# comicition.net
KiCad netlist of a schematic drawn in Altium Designer
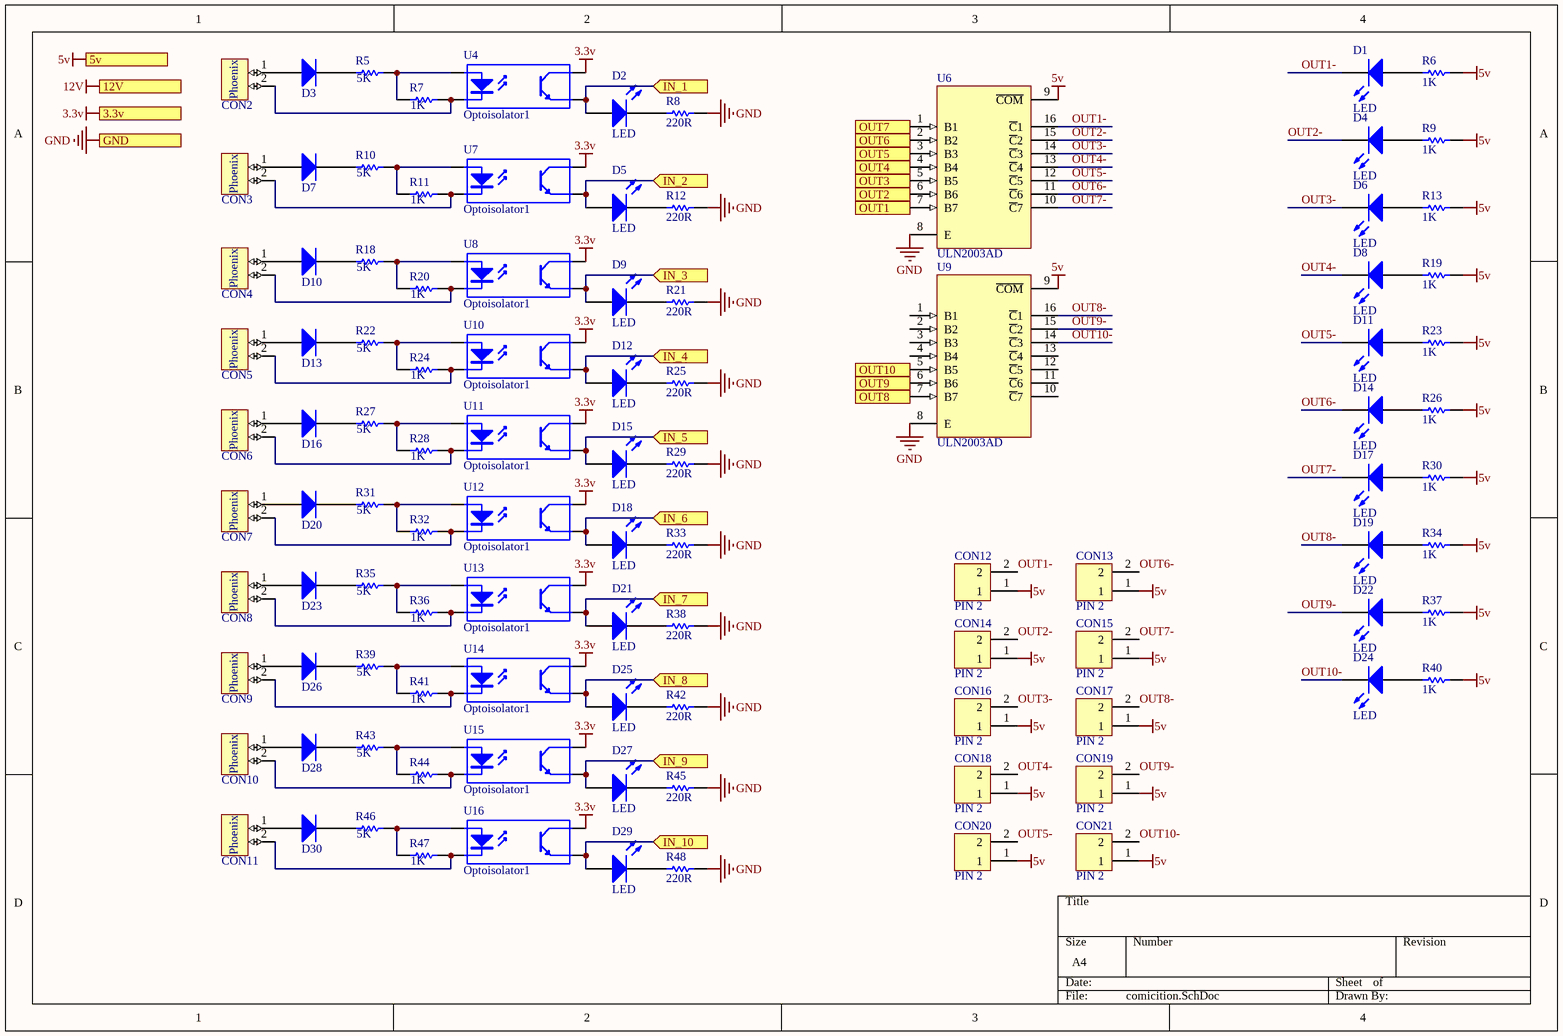
[diagram p0: comicition.SchDoc]

(export (version "E")
  (design (tool "Eeschema 10.0.6"))
  (components
    (comp (ref "CON2")
      (value "PHOENIX 2")
      (footprint "phonix 2")
      (libsource (lib "m_faryabi") (part "PHOENIX 2"))
    )
    (comp (ref "CON3")
      (value "PHOENIX 2")
      (footprint "phonix 2")
      (libsource (lib "m_faryabi") (part "PHOENIX 2"))
    )
    (comp (ref "CON4")
      (value "PHOENIX 2")
      (footprint "phonix 2")
      (libsource (lib "m_faryabi") (part "PHOENIX 2"))
    )
    (comp (ref "CON5")
      (value "PHOENIX 2")
      (footprint "phonix 2")
      (libsource (lib "m_faryabi") (part "PHOENIX 2"))
    )
    (comp (ref "CON6")
      (value "PHOENIX 2")
      (footprint "phonix 2")
      (libsource (lib "m_faryabi") (part "PHOENIX 2"))
    )
    (comp (ref "CON7")
      (value "PHOENIX 2")
      (footprint "phonix 2")
      (libsource (lib "m_faryabi") (part "PHOENIX 2"))
    )
    (comp (ref "CON8")
      (value "PHOENIX 2")
      (footprint "phonix 2")
      (libsource (lib "m_faryabi") (part "PHOENIX 2"))
    )
    (comp (ref "CON9")
      (value "PHOENIX 2")
      (footprint "phonix 2")
      (libsource (lib "m_faryabi") (part "PHOENIX 2"))
    )
    (comp (ref "CON10")
      (value "PHOENIX 2")
      (footprint "phonix 2")
      (libsource (lib "m_faryabi") (part "PHOENIX 2"))
    )
    (comp (ref "CON11")
      (value "PHOENIX 2")
      (footprint "phonix 2")
      (libsource (lib "m_faryabi") (part "PHOENIX 2"))
    )
    (comp (ref "CON12") (value "PIN 2") (footprint "PIN 2") (libsource (lib "m_faryabi") (part "PIN 2")))
    (comp (ref "CON13") (value "PIN 2") (footprint "PIN 2") (libsource (lib "m_faryabi") (part "PIN 2")))
    (comp (ref "CON14") (value "PIN 2") (footprint "PIN 2") (libsource (lib "m_faryabi") (part "PIN 2")))
    (comp (ref "CON15") (value "PIN 2") (footprint "PIN 2") (libsource (lib "m_faryabi") (part "PIN 2")))
    (comp (ref "CON16") (value "PIN 2") (footprint "PIN 2") (libsource (lib "m_faryabi") (part "PIN 2")))
    (comp (ref "CON17") (value "PIN 2") (footprint "PIN 2") (libsource (lib "m_faryabi") (part "PIN 2")))
    (comp (ref "CON18") (value "PIN 2") (footprint "PIN 2") (libsource (lib "m_faryabi") (part "PIN 2")))
    (comp (ref "CON19") (value "PIN 2") (footprint "PIN 2") (libsource (lib "m_faryabi") (part "PIN 2")))
    (comp (ref "CON20") (value "PIN 2") (footprint "PIN 2") (libsource (lib "m_faryabi") (part "PIN 2")))
    (comp (ref "CON21") (value "PIN 2") (footprint "PIN 2") (libsource (lib "m_faryabi") (part "PIN 2")))
    (comp (ref "D1") (value "LED") (footprint "led 5mm") (libsource (lib "m_faryabi") (part "LED")))
    (comp (ref "D2") (value "LED") (footprint "led 5mm") (libsource (lib "m_faryabi") (part "LED")))
    (comp (ref "D3")
      (value "1N4007")
      (footprint "RES 1206 (3216X08L)")
      (libsource (lib "m_faryabi") (part "1N4007"))
    )
    (comp (ref "D4") (value "LED") (footprint "led 5mm") (libsource (lib "m_faryabi") (part "LED")))
    (comp (ref "D5") (value "LED") (footprint "led 5mm") (libsource (lib "m_faryabi") (part "LED")))
    (comp (ref "D6") (value "LED") (footprint "led 5mm") (libsource (lib "m_faryabi") (part "LED")))
    (comp (ref "D7")
      (value "1N4007")
      (footprint "RES 1206 (3216X08L)")
      (libsource (lib "m_faryabi") (part "1N4007"))
    )
    (comp (ref "D8") (value "LED") (footprint "led 5mm") (libsource (lib "m_faryabi") (part "LED")))
    (comp (ref "D9") (value "LED") (footprint "led 5mm") (libsource (lib "m_faryabi") (part "LED")))
    (comp (ref "D10")
      (value "1N4007")
      (footprint "RES 1206 (3216X08L)")
      (libsource (lib "m_faryabi") (part "1N4007"))
    )
    (comp (ref "D11") (value "LED") (footprint "led 5mm") (libsource (lib "m_faryabi") (part "LED")))
    (comp (ref "D12") (value "LED") (footprint "led 5mm") (libsource (lib "m_faryabi") (part "LED")))
    (comp (ref "D13")
      (value "1N4007")
      (footprint "RES 1206 (3216X08L)")
      (libsource (lib "m_faryabi") (part "1N4007"))
    )
    (comp (ref "D14") (value "LED") (footprint "led 5mm") (libsource (lib "m_faryabi") (part "LED")))
    (comp (ref "D15") (value "LED") (footprint "led 5mm") (libsource (lib "m_faryabi") (part "LED")))
    (comp (ref "D16")
      (value "1N4007")
      (footprint "RES 1206 (3216X08L)")
      (libsource (lib "m_faryabi") (part "1N4007"))
    )
    (comp (ref "D17") (value "LED") (footprint "led 5mm") (libsource (lib "m_faryabi") (part "LED")))
    (comp (ref "D18") (value "LED") (footprint "led 5mm") (libsource (lib "m_faryabi") (part "LED")))
    (comp (ref "D19") (value "LED") (footprint "led 5mm") (libsource (lib "m_faryabi") (part "LED")))
    (comp (ref "D20")
      (value "1N4007")
      (footprint "RES 1206 (3216X08L)")
      (libsource (lib "m_faryabi") (part "1N4007"))
    )
    (comp (ref "D21") (value "LED") (footprint "led 5mm") (libsource (lib "m_faryabi") (part "LED")))
    (comp (ref "D22") (value "LED") (footprint "led 5mm") (libsource (lib "m_faryabi") (part "LED")))
    (comp (ref "D23")
      (value "1N4007")
      (footprint "RES 1206 (3216X08L)")
      (libsource (lib "m_faryabi") (part "1N4007"))
    )
    (comp (ref "D24") (value "LED") (footprint "led 5mm") (libsource (lib "m_faryabi") (part "LED")))
    (comp (ref "D25") (value "LED") (footprint "led 5mm") (libsource (lib "m_faryabi") (part "LED")))
    (comp (ref "D26")
      (value "1N4007")
      (footprint "RES 1206 (3216X08L)")
      (libsource (lib "m_faryabi") (part "1N4007"))
    )
    (comp (ref "D27") (value "LED") (footprint "led 5mm") (libsource (lib "m_faryabi") (part "LED")))
    (comp (ref "D28")
      (value "1N4007")
      (footprint "RES 1206 (3216X08L)")
      (libsource (lib "m_faryabi") (part "1N4007"))
    )
    (comp (ref "D29") (value "LED") (footprint "led 5mm") (libsource (lib "m_faryabi") (part "LED")))
    (comp (ref "D30")
      (value "1N4007")
      (footprint "RES 1206 (3216X08L)")
      (libsource (lib "m_faryabi") (part "1N4007"))
    )
    (comp (ref "R5")
      (value "5K")
      (footprint "RES 0805 (2012X06L)")
      (fields (field (name "Comment") "resistor"))
      (libsource (lib "m_faryabi") (part "resistor"))
    )
    (comp (ref "R6")
      (value "1K")
      (footprint "RES 0805 (2012X06L)")
      (fields (field (name "Comment") "resistor"))
      (libsource (lib "m_faryabi") (part "resistor"))
    )
    (comp (ref "R7")
      (value "1K")
      (footprint "RES 0805 (2012X06L)")
      (fields (field (name "Comment") "resistor"))
      (libsource (lib "m_faryabi") (part "resistor"))
    )
    (comp (ref "R8")
      (value "220R")
      (footprint "RES 0805 optional")
      (fields (field (name "Comment") "resistor"))
      (libsource (lib "m_faryabi") (part "resistor"))
    )
    (comp (ref "R9")
      (value "1K")
      (footprint "RES 0805 (2012X06L)")
      (fields (field (name "Comment") "resistor"))
      (libsource (lib "m_faryabi") (part "resistor"))
    )
    (comp (ref "R10")
      (value "5K")
      (footprint "RES 0805 (2012X06L)")
      (fields (field (name "Comment") "resistor"))
      (libsource (lib "m_faryabi") (part "resistor"))
    )
    (comp (ref "R11")
      (value "1K")
      (footprint "RES 0805 (2012X06L)")
      (fields (field (name "Comment") "resistor"))
      (libsource (lib "m_faryabi") (part "resistor"))
    )
    (comp (ref "R12")
      (value "220R")
      (footprint "RES 0805 optional")
      (fields (field (name "Comment") "resistor"))
      (libsource (lib "m_faryabi") (part "resistor"))
    )
    (comp (ref "R13")
      (value "1K")
      (footprint "RES 0805 (2012X06L)")
      (fields (field (name "Comment") "resistor"))
      (libsource (lib "m_faryabi") (part "resistor"))
    )
    (comp (ref "R18")
      (value "5K")
      (footprint "RES 0805 (2012X06L)")
      (fields (field (name "Comment") "resistor"))
      (libsource (lib "m_faryabi") (part "resistor"))
    )
    (comp (ref "R19")
      (value "1K")
      (footprint "RES 0805 (2012X06L)")
      (fields (field (name "Comment") "resistor"))
      (libsource (lib "m_faryabi") (part "resistor"))
    )
    (comp (ref "R20")
      (value "1K")
      (footprint "RES 0805 (2012X06L)")
      (fields (field (name "Comment") "resistor"))
      (libsource (lib "m_faryabi") (part "resistor"))
    )
    (comp (ref "R21")
      (value "220R")
      (footprint "RES 0805 optional")
      (fields (field (name "Comment") "resistor"))
      (libsource (lib "m_faryabi") (part "resistor"))
    )
    (comp (ref "R22")
      (value "5K")
      (footprint "RES 0805 (2012X06L)")
      (fields (field (name "Comment") "resistor"))
      (libsource (lib "m_faryabi") (part "resistor"))
    )
    (comp (ref "R23")
      (value "1K")
      (footprint "RES 0805 (2012X06L)")
      (fields (field (name "Comment") "resistor"))
      (libsource (lib "m_faryabi") (part "resistor"))
    )
    (comp (ref "R24")
      (value "1K")
      (footprint "RES 0805 (2012X06L)")
      (fields (field (name "Comment") "resistor"))
      (libsource (lib "m_faryabi") (part "resistor"))
    )
    (comp (ref "R25")
      (value "220R")
      (footprint "RES 0805 optional")
      (fields (field (name "Comment") "resistor"))
      (libsource (lib "m_faryabi") (part "resistor"))
    )
    (comp (ref "R26")
      (value "1K")
      (footprint "RES 0805 (2012X06L)")
      (fields (field (name "Comment") "resistor"))
      (libsource (lib "m_faryabi") (part "resistor"))
    )
    (comp (ref "R27")
      (value "5K")
      (footprint "RES 0805 (2012X06L)")
      (fields (field (name "Comment") "resistor"))
      (libsource (lib "m_faryabi") (part "resistor"))
    )
    (comp (ref "R28")
      (value "1K")
      (footprint "RES 0805 (2012X06L)")
      (fields (field (name "Comment") "resistor"))
      (libsource (lib "m_faryabi") (part "resistor"))
    )
    (comp (ref "R29")
      (value "220R")
      (footprint "RES 0805 optional")
      (fields (field (name "Comment") "resistor"))
      (libsource (lib "m_faryabi") (part "resistor"))
    )
    (comp (ref "R30")
      (value "1K")
      (footprint "RES 0805 (2012X06L)")
      (fields (field (name "Comment") "resistor"))
      (libsource (lib "m_faryabi") (part "resistor"))
    )
    (comp (ref "R31")
      (value "5K")
      (footprint "RES 0805 (2012X06L)")
      (fields (field (name "Comment") "resistor"))
      (libsource (lib "m_faryabi") (part "resistor"))
    )
    (comp (ref "R32")
      (value "1K")
      (footprint "RES 0805 (2012X06L)")
      (fields (field (name "Comment") "resistor"))
      (libsource (lib "m_faryabi") (part "resistor"))
    )
    (comp (ref "R33")
      (value "220R")
      (footprint "RES 0805 optional")
      (fields (field (name "Comment") "resistor"))
      (libsource (lib "m_faryabi") (part "resistor"))
    )
    (comp (ref "R34")
      (value "1K")
      (footprint "RES 0805 (2012X06L)")
      (fields (field (name "Comment") "resistor"))
      (libsource (lib "m_faryabi") (part "resistor"))
    )
    (comp (ref "R35")
      (value "5K")
      (footprint "RES 0805 (2012X06L)")
      (fields (field (name "Comment") "resistor"))
      (libsource (lib "m_faryabi") (part "resistor"))
    )
    (comp (ref "R36")
      (value "1K")
      (footprint "RES 0805 (2012X06L)")
      (fields (field (name "Comment") "resistor"))
      (libsource (lib "m_faryabi") (part "resistor"))
    )
    (comp (ref "R37")
      (value "1K")
      (footprint "RES 0805 (2012X06L)")
      (fields (field (name "Comment") "resistor"))
      (libsource (lib "m_faryabi") (part "resistor"))
    )
    (comp (ref "R38")
      (value "220R")
      (footprint "RES 0805 optional")
      (fields (field (name "Comment") "resistor"))
      (libsource (lib "m_faryabi") (part "resistor"))
    )
    (comp (ref "R39")
      (value "5K")
      (footprint "RES 0805 (2012X06L)")
      (fields (field (name "Comment") "resistor"))
      (libsource (lib "m_faryabi") (part "resistor"))
    )
    (comp (ref "R40")
      (value "1K")
      (footprint "RES 0805 (2012X06L)")
      (fields (field (name "Comment") "resistor"))
      (libsource (lib "m_faryabi") (part "resistor"))
    )
    (comp (ref "R41")
      (value "1K")
      (footprint "RES 0805 (2012X06L)")
      (fields (field (name "Comment") "resistor"))
      (libsource (lib "m_faryabi") (part "resistor"))
    )
    (comp (ref "R42")
      (value "220R")
      (footprint "RES 0805 optional")
      (fields (field (name "Comment") "resistor"))
      (libsource (lib "m_faryabi") (part "resistor"))
    )
    (comp (ref "R43")
      (value "5K")
      (footprint "RES 0805 (2012X06L)")
      (fields (field (name "Comment") "resistor"))
      (libsource (lib "m_faryabi") (part "resistor"))
    )
    (comp (ref "R44")
      (value "1K")
      (footprint "RES 0805 (2012X06L)")
      (fields (field (name "Comment") "resistor"))
      (libsource (lib "m_faryabi") (part "resistor"))
    )
    (comp (ref "R45")
      (value "220R")
      (footprint "RES 0805 optional")
      (fields (field (name "Comment") "resistor"))
      (libsource (lib "m_faryabi") (part "resistor"))
    )
    (comp (ref "R46")
      (value "5K")
      (footprint "RES 0805 (2012X06L)")
      (fields (field (name "Comment") "resistor"))
      (libsource (lib "m_faryabi") (part "resistor"))
    )
    (comp (ref "R47")
      (value "1K")
      (footprint "RES 0805 (2012X06L)")
      (fields (field (name "Comment") "resistor"))
      (libsource (lib "m_faryabi") (part "resistor"))
    )
    (comp (ref "R48")
      (value "220R")
      (footprint "RES 0805 optional")
      (fields (field (name "Comment") "resistor"))
      (libsource (lib "m_faryabi") (part "resistor"))
    )
    (comp (ref "U4")
      (value "Optoisolator1")
      (footprint "DIP-4")
      (description "4-Pin Phototransistor Optocoupler")
      (fields (field (name "PUBLISHER") "Altium Limited"))
      (libsource (lib "Miscellaneous Devices") (part "Optoisolator1"))
    )
    (comp (ref "U6")
      (value "ULN2003AD")
      (footprint "D016_N")
      (description "Darlington Transistor Array")
      (fields (field (name "PUBLISHER") "Altium Limited"))
      (libsource (lib "TI Interface Darlington Driver") (part "ULN2003AD"))
    )
    (comp (ref "U7")
      (value "Optoisolator1")
      (footprint "DIP-4")
      (description "4-Pin Phototransistor Optocoupler")
      (fields (field (name "PUBLISHER") "Altium Limited"))
      (libsource (lib "Miscellaneous Devices") (part "Optoisolator1"))
    )
    (comp (ref "U8")
      (value "Optoisolator1")
      (footprint "DIP-4")
      (description "4-Pin Phototransistor Optocoupler")
      (fields (field (name "PUBLISHER") "Altium Limited"))
      (libsource (lib "Miscellaneous Devices") (part "Optoisolator1"))
    )
    (comp (ref "U9")
      (value "ULN2003AD")
      (footprint "D016_N")
      (description "Darlington Transistor Array")
      (fields (field (name "PUBLISHER") "Altium Limited"))
      (libsource (lib "TI Interface Darlington Driver") (part "ULN2003AD"))
    )
    (comp (ref "U10")
      (value "Optoisolator1")
      (footprint "DIP-4")
      (description "4-Pin Phototransistor Optocoupler")
      (fields (field (name "PUBLISHER") "Altium Limited"))
      (libsource (lib "Miscellaneous Devices") (part "Optoisolator1"))
    )
    (comp (ref "U11")
      (value "Optoisolator1")
      (footprint "DIP-4")
      (description "4-Pin Phototransistor Optocoupler")
      (fields (field (name "PUBLISHER") "Altium Limited"))
      (libsource (lib "Miscellaneous Devices") (part "Optoisolator1"))
    )
    (comp (ref "U12")
      (value "Optoisolator1")
      (footprint "DIP-4")
      (description "4-Pin Phototransistor Optocoupler")
      (fields (field (name "PUBLISHER") "Altium Limited"))
      (libsource (lib "Miscellaneous Devices") (part "Optoisolator1"))
    )
    (comp (ref "U13")
      (value "Optoisolator1")
      (footprint "DIP-4")
      (description "4-Pin Phototransistor Optocoupler")
      (fields (field (name "PUBLISHER") "Altium Limited"))
      (libsource (lib "Miscellaneous Devices") (part "Optoisolator1"))
    )
    (comp (ref "U14")
      (value "Optoisolator1")
      (footprint "DIP-4")
      (description "4-Pin Phototransistor Optocoupler")
      (fields (field (name "PUBLISHER") "Altium Limited"))
      (libsource (lib "Miscellaneous Devices") (part "Optoisolator1"))
    )
    (comp (ref "U15")
      (value "Optoisolator1")
      (footprint "DIP-4")
      (description "4-Pin Phototransistor Optocoupler")
      (fields (field (name "PUBLISHER") "Altium Limited"))
      (libsource (lib "Miscellaneous Devices") (part "Optoisolator1"))
    )
    (comp (ref "U16")
      (value "Optoisolator1")
      (footprint "DIP-4")
      (description "4-Pin Phototransistor Optocoupler")
      (fields (field (name "PUBLISHER") "Altium Limited"))
      (libsource (lib "Miscellaneous Devices") (part "Optoisolator1"))
    )
  )
  (nets
    (net (code "1") (name "/IN_1") (class "Default")
      (node (ref "D2") (pin "1") (pinfunction "A_1") (pintype "passive"))
      (node (ref "U4") (pin "3") (pinfunction "E_3") (pintype "passive"))
    )
    (net (code "2") (name "/IN_2") (class "Default")
      (node (ref "D5") (pin "1") (pinfunction "A_1") (pintype "passive"))
      (node (ref "U7") (pin "3") (pinfunction "E_3") (pintype "passive"))
    )
    (net (code "3") (name "/IN_3") (class "Default")
      (node (ref "D9") (pin "1") (pinfunction "A_1") (pintype "passive"))
      (node (ref "U8") (pin "3") (pinfunction "E_3") (pintype "passive"))
    )
    (net (code "4") (name "/IN_4") (class "Default")
      (node (ref "D12") (pin "1") (pinfunction "A_1") (pintype "passive"))
      (node (ref "U10") (pin "3") (pinfunction "E_3") (pintype "passive"))
    )
    (net (code "5") (name "/IN_5") (class "Default")
      (node (ref "D15") (pin "1") (pinfunction "A_1") (pintype "passive"))
      (node (ref "U11") (pin "3") (pinfunction "E_3") (pintype "passive"))
    )
    (net (code "6") (name "/IN_6") (class "Default")
      (node (ref "D18") (pin "1") (pinfunction "A_1") (pintype "passive"))
      (node (ref "U12") (pin "3") (pinfunction "E_3") (pintype "passive"))
    )
    (net (code "7") (name "/IN_7") (class "Default")
      (node (ref "D21") (pin "1") (pinfunction "A_1") (pintype "passive"))
      (node (ref "U13") (pin "3") (pinfunction "E_3") (pintype "passive"))
    )
    (net (code "8") (name "/IN_8") (class "Default")
      (node (ref "D25") (pin "1") (pinfunction "A_1") (pintype "passive"))
      (node (ref "U14") (pin "3") (pinfunction "E_3") (pintype "passive"))
    )
    (net (code "9") (name "/IN_9") (class "Default")
      (node (ref "D27") (pin "1") (pinfunction "A_1") (pintype "passive"))
      (node (ref "U15") (pin "3") (pinfunction "E_3") (pintype "passive"))
    )
    (net (code "10") (name "/IN_10") (class "Default")
      (node (ref "D29") (pin "1") (pinfunction "A_1") (pintype "passive"))
      (node (ref "U16") (pin "3") (pinfunction "E_3") (pintype "passive"))
    )
    (net (code "11") (name "/OUT1") (class "Default")
      (node (ref "U6") (pin "7") (pinfunction "B7_7") (pintype "input"))
    )
    (net (code "12") (name "/OUT1-") (class "Default")
      (node (ref "CON12") (pin "2") (pinfunction "2_2") (pintype "passive"))
      (node (ref "D1") (pin "2") (pinfunction "K_2") (pintype "passive"))
      (node (ref "U6") (pin "16") (pinfunction "~{C}1_16") (pintype "open_collector"))
    )
    (net (code "13") (name "/OUT2") (class "Default")
      (node (ref "U6") (pin "6") (pinfunction "B6_6") (pintype "input"))
    )
    (net (code "14") (name "/OUT2-") (class "Default")
      (node (ref "CON14") (pin "2") (pinfunction "2_2") (pintype "passive"))
      (node (ref "D4") (pin "2") (pinfunction "K_2") (pintype "passive"))
      (node (ref "U6") (pin "15") (pinfunction "~{C}2_15") (pintype "open_collector"))
    )
    (net (code "15") (name "/OUT3") (class "Default")
      (node (ref "U6") (pin "5") (pinfunction "B5_5") (pintype "input"))
    )
    (net (code "16") (name "/OUT3-") (class "Default")
      (node (ref "CON16") (pin "2") (pinfunction "2_2") (pintype "passive"))
      (node (ref "D6") (pin "2") (pinfunction "K_2") (pintype "passive"))
      (node (ref "U6") (pin "14") (pinfunction "~{C}3_14") (pintype "open_collector"))
    )
    (net (code "17") (name "/OUT4") (class "Default")
      (node (ref "U6") (pin "4") (pinfunction "B4_4") (pintype "input"))
    )
    (net (code "18") (name "/OUT4-") (class "Default")
      (node (ref "CON18") (pin "2") (pinfunction "2_2") (pintype "passive"))
      (node (ref "D8") (pin "2") (pinfunction "K_2") (pintype "passive"))
      (node (ref "U6") (pin "13") (pinfunction "~{C}4_13") (pintype "open_collector"))
    )
    (net (code "19") (name "/OUT5") (class "Default")
      (node (ref "U6") (pin "3") (pinfunction "B3_3") (pintype "input"))
    )
    (net (code "20") (name "/OUT5-") (class "Default")
      (node (ref "CON20") (pin "2") (pinfunction "2_2") (pintype "passive"))
      (node (ref "D11") (pin "2") (pinfunction "K_2") (pintype "passive"))
      (node (ref "U6") (pin "12") (pinfunction "~{C}5_12") (pintype "open_collector"))
    )
    (net (code "21") (name "/OUT6") (class "Default")
      (node (ref "U6") (pin "2") (pinfunction "B2_2") (pintype "input"))
    )
    (net (code "22") (name "/OUT6-") (class "Default")
      (node (ref "CON13") (pin "2") (pinfunction "2_2") (pintype "passive"))
      (node (ref "D14") (pin "2") (pinfunction "K_2") (pintype "passive"))
      (node (ref "U6") (pin "11") (pinfunction "~{C}6_11") (pintype "open_collector"))
    )
    (net (code "23") (name "/OUT7") (class "Default")
      (node (ref "U6") (pin "1") (pinfunction "B1_1") (pintype "input"))
    )
    (net (code "24") (name "/OUT7-") (class "Default")
      (node (ref "CON15") (pin "2") (pinfunction "2_2") (pintype "passive"))
      (node (ref "D17") (pin "2") (pinfunction "K_2") (pintype "passive"))
      (node (ref "U6") (pin "10") (pinfunction "~{C}7_10") (pintype "open_collector"))
    )
    (net (code "25") (name "/OUT8") (class "Default")
      (node (ref "U9") (pin "7") (pinfunction "B7_7") (pintype "input"))
    )
    (net (code "26") (name "/OUT8-") (class "Default")
      (node (ref "CON17") (pin "2") (pinfunction "2_2") (pintype "passive"))
      (node (ref "D19") (pin "2") (pinfunction "K_2") (pintype "passive"))
      (node (ref "U9") (pin "16") (pinfunction "~{C}1_16") (pintype "open_collector"))
    )
    (net (code "27") (name "/OUT9") (class "Default")
      (node (ref "U9") (pin "6") (pinfunction "B6_6") (pintype "input"))
    )
    (net (code "28") (name "/OUT9-") (class "Default")
      (node (ref "CON19") (pin "2") (pinfunction "2_2") (pintype "passive"))
      (node (ref "D22") (pin "2") (pinfunction "K_2") (pintype "passive"))
      (node (ref "U9") (pin "15") (pinfunction "~{C}2_15") (pintype "open_collector"))
    )
    (net (code "29") (name "/OUT10") (class "Default")
      (node (ref "U9") (pin "5") (pinfunction "B5_5") (pintype "input"))
    )
    (net (code "30") (name "/OUT10-") (class "Default")
      (node (ref "CON21") (pin "2") (pinfunction "2_2") (pintype "passive"))
      (node (ref "D24") (pin "2") (pinfunction "K_2") (pintype "passive"))
      (node (ref "U9") (pin "14") (pinfunction "~{C}3_14") (pintype "open_collector"))
    )
    (net (code "31") (name "3.3v") (class "Default")
      (node (ref "U10") (pin "4") (pinfunction "C_4") (pintype "passive"))
      (node (ref "U11") (pin "4") (pinfunction "C_4") (pintype "passive"))
      (node (ref "U12") (pin "4") (pinfunction "C_4") (pintype "passive"))
      (node (ref "U13") (pin "4") (pinfunction "C_4") (pintype "passive"))
      (node (ref "U14") (pin "4") (pinfunction "C_4") (pintype "passive"))
      (node (ref "U15") (pin "4") (pinfunction "C_4") (pintype "passive"))
      (node (ref "U16") (pin "4") (pinfunction "C_4") (pintype "passive"))
      (node (ref "U4") (pin "4") (pinfunction "C_4") (pintype "passive"))
      (node (ref "U7") (pin "4") (pinfunction "C_4") (pintype "passive"))
      (node (ref "U8") (pin "4") (pinfunction "C_4") (pintype "passive"))
    )
    (net (code "32") (name "5v") (class "Default")
      (node (ref "CON12") (pin "1") (pinfunction "1_1") (pintype "passive"))
      (node (ref "CON13") (pin "1") (pinfunction "1_1") (pintype "passive"))
      (node (ref "CON14") (pin "1") (pinfunction "1_1") (pintype "passive"))
      (node (ref "CON15") (pin "1") (pinfunction "1_1") (pintype "passive"))
      (node (ref "CON16") (pin "1") (pinfunction "1_1") (pintype "passive"))
      (node (ref "CON17") (pin "1") (pinfunction "1_1") (pintype "passive"))
      (node (ref "CON18") (pin "1") (pinfunction "1_1") (pintype "passive"))
      (node (ref "CON19") (pin "1") (pinfunction "1_1") (pintype "passive"))
      (node (ref "CON20") (pin "1") (pinfunction "1_1") (pintype "passive"))
      (node (ref "CON21") (pin "1") (pinfunction "1_1") (pintype "passive"))
      (node (ref "R13") (pin "2") (pinfunction "2_2") (pintype "passive"))
      (node (ref "R19") (pin "2") (pinfunction "2_2") (pintype "passive"))
      (node (ref "R23") (pin "2") (pinfunction "2_2") (pintype "passive"))
      (node (ref "R26") (pin "2") (pinfunction "2_2") (pintype "passive"))
      (node (ref "R30") (pin "2") (pinfunction "2_2") (pintype "passive"))
      (node (ref "R34") (pin "2") (pinfunction "2_2") (pintype "passive"))
      (node (ref "R37") (pin "2") (pinfunction "2_2") (pintype "passive"))
      (node (ref "R40") (pin "2") (pinfunction "2_2") (pintype "passive"))
      (node (ref "R6") (pin "2") (pinfunction "2_2") (pintype "passive"))
      (node (ref "R9") (pin "2") (pinfunction "2_2") (pintype "passive"))
      (node (ref "U6") (pin "9") (pinfunction "~{COM}_9") (pintype "passive"))
      (node (ref "U9") (pin "9") (pinfunction "~{COM}_9") (pintype "passive"))
    )
    (net (code "34") (name "GND") (class "Default")
      (node (ref "R12") (pin "1") (pinfunction "1_1") (pintype "passive"))
      (node (ref "R21") (pin "1") (pinfunction "1_1") (pintype "passive"))
      (node (ref "R25") (pin "1") (pinfunction "1_1") (pintype "passive"))
      (node (ref "R29") (pin "1") (pinfunction "1_1") (pintype "passive"))
      (node (ref "R33") (pin "1") (pinfunction "1_1") (pintype "passive"))
      (node (ref "R38") (pin "1") (pinfunction "1_1") (pintype "passive"))
      (node (ref "R42") (pin "1") (pinfunction "1_1") (pintype "passive"))
      (node (ref "R45") (pin "1") (pinfunction "1_1") (pintype "passive"))
      (node (ref "R48") (pin "1") (pinfunction "1_1") (pintype "passive"))
      (node (ref "R8") (pin "1") (pinfunction "1_1") (pintype "passive"))
      (node (ref "U6") (pin "8") (pinfunction "E_8") (pintype "power_in"))
      (node (ref "U9") (pin "8") (pinfunction "E_8") (pintype "power_in"))
    )
    (net (code "35") (name "Net-(D1-A)") (class "Default")
      (node (ref "D1") (pin "1") (pinfunction "A_1") (pintype "passive"))
      (node (ref "R6") (pin "1") (pinfunction "1_1") (pintype "passive"))
    )
    (net (code "36") (name "Net-(D2-K)") (class "Default")
      (node (ref "D2") (pin "2") (pinfunction "K_2") (pintype "passive"))
      (node (ref "R8") (pin "2") (pinfunction "2_2") (pintype "passive"))
    )
    (net (code "37") (name "Net-(D3-A)") (class "Default")
      (node (ref "CON2") (pin "1") (pinfunction "1_1") (pintype "bidirectional"))
      (node (ref "D3") (pin "1") (pinfunction "A_1") (pintype "passive"))
    )
    (net (code "38") (name "Net-(D3-K)") (class "Default")
      (node (ref "D3") (pin "2") (pinfunction "K_2") (pintype "passive"))
      (node (ref "R5") (pin "1") (pinfunction "1_1") (pintype "passive"))
    )
    (net (code "39") (name "Net-(D4-A)") (class "Default")
      (node (ref "D4") (pin "1") (pinfunction "A_1") (pintype "passive"))
      (node (ref "R9") (pin "1") (pinfunction "1_1") (pintype "passive"))
    )
    (net (code "40") (name "Net-(D5-K)") (class "Default")
      (node (ref "D5") (pin "2") (pinfunction "K_2") (pintype "passive"))
      (node (ref "R12") (pin "2") (pinfunction "2_2") (pintype "passive"))
    )
    (net (code "41") (name "Net-(D6-A)") (class "Default")
      (node (ref "D6") (pin "1") (pinfunction "A_1") (pintype "passive"))
      (node (ref "R13") (pin "1") (pinfunction "1_1") (pintype "passive"))
    )
    (net (code "42") (name "Net-(D7-A)") (class "Default")
      (node (ref "CON3") (pin "1") (pinfunction "1_1") (pintype "bidirectional"))
      (node (ref "D7") (pin "1") (pinfunction "A_1") (pintype "passive"))
    )
    (net (code "43") (name "Net-(D7-K)") (class "Default")
      (node (ref "D7") (pin "2") (pinfunction "K_2") (pintype "passive"))
      (node (ref "R10") (pin "1") (pinfunction "1_1") (pintype "passive"))
    )
    (net (code "44") (name "Net-(D8-A)") (class "Default")
      (node (ref "D8") (pin "1") (pinfunction "A_1") (pintype "passive"))
      (node (ref "R19") (pin "1") (pinfunction "1_1") (pintype "passive"))
    )
    (net (code "45") (name "Net-(D9-K)") (class "Default")
      (node (ref "D9") (pin "2") (pinfunction "K_2") (pintype "passive"))
      (node (ref "R21") (pin "2") (pinfunction "2_2") (pintype "passive"))
    )
    (net (code "46") (name "Net-(D10-A)") (class "Default")
      (node (ref "CON4") (pin "1") (pinfunction "1_1") (pintype "bidirectional"))
      (node (ref "D10") (pin "1") (pinfunction "A_1") (pintype "passive"))
    )
    (net (code "47") (name "Net-(D10-K)") (class "Default")
      (node (ref "D10") (pin "2") (pinfunction "K_2") (pintype "passive"))
      (node (ref "R18") (pin "1") (pinfunction "1_1") (pintype "passive"))
    )
    (net (code "48") (name "Net-(D11-A)") (class "Default")
      (node (ref "D11") (pin "1") (pinfunction "A_1") (pintype "passive"))
      (node (ref "R23") (pin "1") (pinfunction "1_1") (pintype "passive"))
    )
    (net (code "49") (name "Net-(D12-K)") (class "Default")
      (node (ref "D12") (pin "2") (pinfunction "K_2") (pintype "passive"))
      (node (ref "R25") (pin "2") (pinfunction "2_2") (pintype "passive"))
    )
    (net (code "50") (name "Net-(D13-A)") (class "Default")
      (node (ref "CON5") (pin "1") (pinfunction "1_1") (pintype "bidirectional"))
      (node (ref "D13") (pin "1") (pinfunction "A_1") (pintype "passive"))
    )
    (net (code "51") (name "Net-(D13-K)") (class "Default")
      (node (ref "D13") (pin "2") (pinfunction "K_2") (pintype "passive"))
      (node (ref "R22") (pin "1") (pinfunction "1_1") (pintype "passive"))
    )
    (net (code "52") (name "Net-(D14-A)") (class "Default")
      (node (ref "D14") (pin "1") (pinfunction "A_1") (pintype "passive"))
      (node (ref "R26") (pin "1") (pinfunction "1_1") (pintype "passive"))
    )
    (net (code "53") (name "Net-(D15-K)") (class "Default")
      (node (ref "D15") (pin "2") (pinfunction "K_2") (pintype "passive"))
      (node (ref "R29") (pin "2") (pinfunction "2_2") (pintype "passive"))
    )
    (net (code "54") (name "Net-(D16-A)") (class "Default")
      (node (ref "CON6") (pin "1") (pinfunction "1_1") (pintype "bidirectional"))
      (node (ref "D16") (pin "1") (pinfunction "A_1") (pintype "passive"))
    )
    (net (code "55") (name "Net-(D16-K)") (class "Default")
      (node (ref "D16") (pin "2") (pinfunction "K_2") (pintype "passive"))
      (node (ref "R27") (pin "1") (pinfunction "1_1") (pintype "passive"))
    )
    (net (code "56") (name "Net-(D17-A)") (class "Default")
      (node (ref "D17") (pin "1") (pinfunction "A_1") (pintype "passive"))
      (node (ref "R30") (pin "1") (pinfunction "1_1") (pintype "passive"))
    )
    (net (code "57") (name "Net-(D18-K)") (class "Default")
      (node (ref "D18") (pin "2") (pinfunction "K_2") (pintype "passive"))
      (node (ref "R33") (pin "2") (pinfunction "2_2") (pintype "passive"))
    )
    (net (code "58") (name "Net-(D19-A)") (class "Default")
      (node (ref "D19") (pin "1") (pinfunction "A_1") (pintype "passive"))
      (node (ref "R34") (pin "1") (pinfunction "1_1") (pintype "passive"))
    )
    (net (code "59") (name "Net-(D20-A)") (class "Default")
      (node (ref "CON7") (pin "1") (pinfunction "1_1") (pintype "bidirectional"))
      (node (ref "D20") (pin "1") (pinfunction "A_1") (pintype "passive"))
    )
    (net (code "60") (name "Net-(D20-K)") (class "Default")
      (node (ref "D20") (pin "2") (pinfunction "K_2") (pintype "passive"))
      (node (ref "R31") (pin "1") (pinfunction "1_1") (pintype "passive"))
    )
    (net (code "61") (name "Net-(D21-K)") (class "Default")
      (node (ref "D21") (pin "2") (pinfunction "K_2") (pintype "passive"))
      (node (ref "R38") (pin "2") (pinfunction "2_2") (pintype "passive"))
    )
    (net (code "62") (name "Net-(D22-A)") (class "Default")
      (node (ref "D22") (pin "1") (pinfunction "A_1") (pintype "passive"))
      (node (ref "R37") (pin "1") (pinfunction "1_1") (pintype "passive"))
    )
    (net (code "63") (name "Net-(D23-A)") (class "Default")
      (node (ref "CON8") (pin "1") (pinfunction "1_1") (pintype "bidirectional"))
      (node (ref "D23") (pin "1") (pinfunction "A_1") (pintype "passive"))
    )
    (net (code "64") (name "Net-(D23-K)") (class "Default")
      (node (ref "D23") (pin "2") (pinfunction "K_2") (pintype "passive"))
      (node (ref "R35") (pin "1") (pinfunction "1_1") (pintype "passive"))
    )
    (net (code "65") (name "Net-(D24-A)") (class "Default")
      (node (ref "D24") (pin "1") (pinfunction "A_1") (pintype "passive"))
      (node (ref "R40") (pin "1") (pinfunction "1_1") (pintype "passive"))
    )
    (net (code "66") (name "Net-(D25-K)") (class "Default")
      (node (ref "D25") (pin "2") (pinfunction "K_2") (pintype "passive"))
      (node (ref "R42") (pin "2") (pinfunction "2_2") (pintype "passive"))
    )
    (net (code "67") (name "Net-(D26-A)") (class "Default")
      (node (ref "CON9") (pin "1") (pinfunction "1_1") (pintype "bidirectional"))
      (node (ref "D26") (pin "1") (pinfunction "A_1") (pintype "passive"))
    )
    (net (code "68") (name "Net-(D26-K)") (class "Default")
      (node (ref "D26") (pin "2") (pinfunction "K_2") (pintype "passive"))
      (node (ref "R39") (pin "1") (pinfunction "1_1") (pintype "passive"))
    )
    (net (code "69") (name "Net-(D27-K)") (class "Default")
      (node (ref "D27") (pin "2") (pinfunction "K_2") (pintype "passive"))
      (node (ref "R45") (pin "2") (pinfunction "2_2") (pintype "passive"))
    )
    (net (code "70") (name "Net-(D28-A)") (class "Default")
      (node (ref "CON10") (pin "1") (pinfunction "1_1") (pintype "bidirectional"))
      (node (ref "D28") (pin "1") (pinfunction "A_1") (pintype "passive"))
    )
    (net (code "71") (name "Net-(D28-K)") (class "Default")
      (node (ref "D28") (pin "2") (pinfunction "K_2") (pintype "passive"))
      (node (ref "R43") (pin "1") (pinfunction "1_1") (pintype "passive"))
    )
    (net (code "72") (name "Net-(D29-K)") (class "Default")
      (node (ref "D29") (pin "2") (pinfunction "K_2") (pintype "passive"))
      (node (ref "R48") (pin "2") (pinfunction "2_2") (pintype "passive"))
    )
    (net (code "73") (name "Net-(D30-A)") (class "Default")
      (node (ref "CON11") (pin "1") (pinfunction "1_1") (pintype "bidirectional"))
      (node (ref "D30") (pin "1") (pinfunction "A_1") (pintype "passive"))
    )
    (net (code "74") (name "Net-(D30-K)") (class "Default")
      (node (ref "D30") (pin "2") (pinfunction "K_2") (pintype "passive"))
      (node (ref "R46") (pin "1") (pinfunction "1_1") (pintype "passive"))
    )
    (net (code "75") (name "Net-(U4-A)") (class "Default")
      (node (ref "R5") (pin "2") (pinfunction "2_2") (pintype "passive"))
      (node (ref "R7") (pin "1") (pinfunction "1_1") (pintype "passive"))
      (node (ref "U4") (pin "1") (pinfunction "A_1") (pintype "passive"))
    )
    (net (code "76") (name "Net-(U4-K)") (class "Default")
      (node (ref "CON2") (pin "2") (pinfunction "2_2") (pintype "bidirectional"))
      (node (ref "R7") (pin "2") (pinfunction "2_2") (pintype "passive"))
      (node (ref "U4") (pin "2") (pinfunction "K_2") (pintype "passive"))
    )
    (net (code "77") (name "Net-(U7-A)") (class "Default")
      (node (ref "R10") (pin "2") (pinfunction "2_2") (pintype "passive"))
      (node (ref "R11") (pin "1") (pinfunction "1_1") (pintype "passive"))
      (node (ref "U7") (pin "1") (pinfunction "A_1") (pintype "passive"))
    )
    (net (code "78") (name "Net-(U7-K)") (class "Default")
      (node (ref "CON3") (pin "2") (pinfunction "2_2") (pintype "bidirectional"))
      (node (ref "R11") (pin "2") (pinfunction "2_2") (pintype "passive"))
      (node (ref "U7") (pin "2") (pinfunction "K_2") (pintype "passive"))
    )
    (net (code "79") (name "Net-(U8-A)") (class "Default")
      (node (ref "R18") (pin "2") (pinfunction "2_2") (pintype "passive"))
      (node (ref "R20") (pin "1") (pinfunction "1_1") (pintype "passive"))
      (node (ref "U8") (pin "1") (pinfunction "A_1") (pintype "passive"))
    )
    (net (code "80") (name "Net-(U8-K)") (class "Default")
      (node (ref "CON4") (pin "2") (pinfunction "2_2") (pintype "bidirectional"))
      (node (ref "R20") (pin "2") (pinfunction "2_2") (pintype "passive"))
      (node (ref "U8") (pin "2") (pinfunction "K_2") (pintype "passive"))
    )
    (net (code "81") (name "Net-(U10-A)") (class "Default")
      (node (ref "R22") (pin "2") (pinfunction "2_2") (pintype "passive"))
      (node (ref "R24") (pin "1") (pinfunction "1_1") (pintype "passive"))
      (node (ref "U10") (pin "1") (pinfunction "A_1") (pintype "passive"))
    )
    (net (code "82") (name "Net-(U10-K)") (class "Default")
      (node (ref "CON5") (pin "2") (pinfunction "2_2") (pintype "bidirectional"))
      (node (ref "R24") (pin "2") (pinfunction "2_2") (pintype "passive"))
      (node (ref "U10") (pin "2") (pinfunction "K_2") (pintype "passive"))
    )
    (net (code "83") (name "Net-(U11-A)") (class "Default")
      (node (ref "R27") (pin "2") (pinfunction "2_2") (pintype "passive"))
      (node (ref "R28") (pin "1") (pinfunction "1_1") (pintype "passive"))
      (node (ref "U11") (pin "1") (pinfunction "A_1") (pintype "passive"))
    )
    (net (code "84") (name "Net-(U11-K)") (class "Default")
      (node (ref "CON6") (pin "2") (pinfunction "2_2") (pintype "bidirectional"))
      (node (ref "R28") (pin "2") (pinfunction "2_2") (pintype "passive"))
      (node (ref "U11") (pin "2") (pinfunction "K_2") (pintype "passive"))
    )
    (net (code "85") (name "Net-(U12-A)") (class "Default")
      (node (ref "R31") (pin "2") (pinfunction "2_2") (pintype "passive"))
      (node (ref "R32") (pin "1") (pinfunction "1_1") (pintype "passive"))
      (node (ref "U12") (pin "1") (pinfunction "A_1") (pintype "passive"))
    )
    (net (code "86") (name "Net-(U12-K)") (class "Default")
      (node (ref "CON7") (pin "2") (pinfunction "2_2") (pintype "bidirectional"))
      (node (ref "R32") (pin "2") (pinfunction "2_2") (pintype "passive"))
      (node (ref "U12") (pin "2") (pinfunction "K_2") (pintype "passive"))
    )
    (net (code "87") (name "Net-(U13-A)") (class "Default")
      (node (ref "R35") (pin "2") (pinfunction "2_2") (pintype "passive"))
      (node (ref "R36") (pin "1") (pinfunction "1_1") (pintype "passive"))
      (node (ref "U13") (pin "1") (pinfunction "A_1") (pintype "passive"))
    )
    (net (code "88") (name "Net-(U13-K)") (class "Default")
      (node (ref "CON8") (pin "2") (pinfunction "2_2") (pintype "bidirectional"))
      (node (ref "R36") (pin "2") (pinfunction "2_2") (pintype "passive"))
      (node (ref "U13") (pin "2") (pinfunction "K_2") (pintype "passive"))
    )
    (net (code "89") (name "Net-(U14-A)") (class "Default")
      (node (ref "R39") (pin "2") (pinfunction "2_2") (pintype "passive"))
      (node (ref "R41") (pin "1") (pinfunction "1_1") (pintype "passive"))
      (node (ref "U14") (pin "1") (pinfunction "A_1") (pintype "passive"))
    )
    (net (code "90") (name "Net-(U14-K)") (class "Default")
      (node (ref "CON9") (pin "2") (pinfunction "2_2") (pintype "bidirectional"))
      (node (ref "R41") (pin "2") (pinfunction "2_2") (pintype "passive"))
      (node (ref "U14") (pin "2") (pinfunction "K_2") (pintype "passive"))
    )
    (net (code "91") (name "Net-(U15-A)") (class "Default")
      (node (ref "R43") (pin "2") (pinfunction "2_2") (pintype "passive"))
      (node (ref "R44") (pin "1") (pinfunction "1_1") (pintype "passive"))
      (node (ref "U15") (pin "1") (pinfunction "A_1") (pintype "passive"))
    )
    (net (code "92") (name "Net-(U15-K)") (class "Default")
      (node (ref "CON10") (pin "2") (pinfunction "2_2") (pintype "bidirectional"))
      (node (ref "R44") (pin "2") (pinfunction "2_2") (pintype "passive"))
      (node (ref "U15") (pin "2") (pinfunction "K_2") (pintype "passive"))
    )
    (net (code "93") (name "Net-(U16-A)") (class "Default")
      (node (ref "R46") (pin "2") (pinfunction "2_2") (pintype "passive"))
      (node (ref "R47") (pin "1") (pinfunction "1_1") (pintype "passive"))
      (node (ref "U16") (pin "1") (pinfunction "A_1") (pintype "passive"))
    )
    (net (code "94") (name "Net-(U16-K)") (class "Default")
      (node (ref "CON11") (pin "2") (pinfunction "2_2") (pintype "bidirectional"))
      (node (ref "R47") (pin "2") (pinfunction "2_2") (pintype "passive"))
      (node (ref "U16") (pin "2") (pinfunction "K_2") (pintype "passive"))
    )
    (net (code "95") (name "unconnected-(U9-B1-Pad1)") (class "Default")
      (node (ref "U9") (pin "1") (pinfunction "B1_1") (pintype "input"))
    )
    (net (code "96") (name "unconnected-(U9-B2-Pad2)") (class "Default")
      (node (ref "U9") (pin "2") (pinfunction "B2_2") (pintype "input"))
    )
    (net (code "97") (name "unconnected-(U9-B3-Pad3)") (class "Default")
      (node (ref "U9") (pin "3") (pinfunction "B3_3") (pintype "input"))
    )
    (net (code "98") (name "unconnected-(U9-B4-Pad4)") (class "Default")
      (node (ref "U9") (pin "4") (pinfunction "B4_4") (pintype "input"))
    )
    (net (code "99") (name "unconnected-(U9-~{C}4-Pad13)") (class "Default")
      (node (ref "U9") (pin "13") (pinfunction "~{C}4_13") (pintype "open_collector"))
    )
    (net (code "100") (name "unconnected-(U9-~{C}5-Pad12)") (class "Default")
      (node (ref "U9") (pin "12") (pinfunction "~{C}5_12") (pintype "open_collector"))
    )
    (net (code "101") (name "unconnected-(U9-~{C}6-Pad11)") (class "Default")
      (node (ref "U9") (pin "11") (pinfunction "~{C}6_11") (pintype "open_collector"))
    )
    (net (code "102") (name "unconnected-(U9-~{C}7-Pad10)") (class "Default")
      (node (ref "U9") (pin "10") (pinfunction "~{C}7_10") (pintype "open_collector"))
    )
  )
)
